# Main.net
KiCad netlist of a schematic drawn in Altium Designer
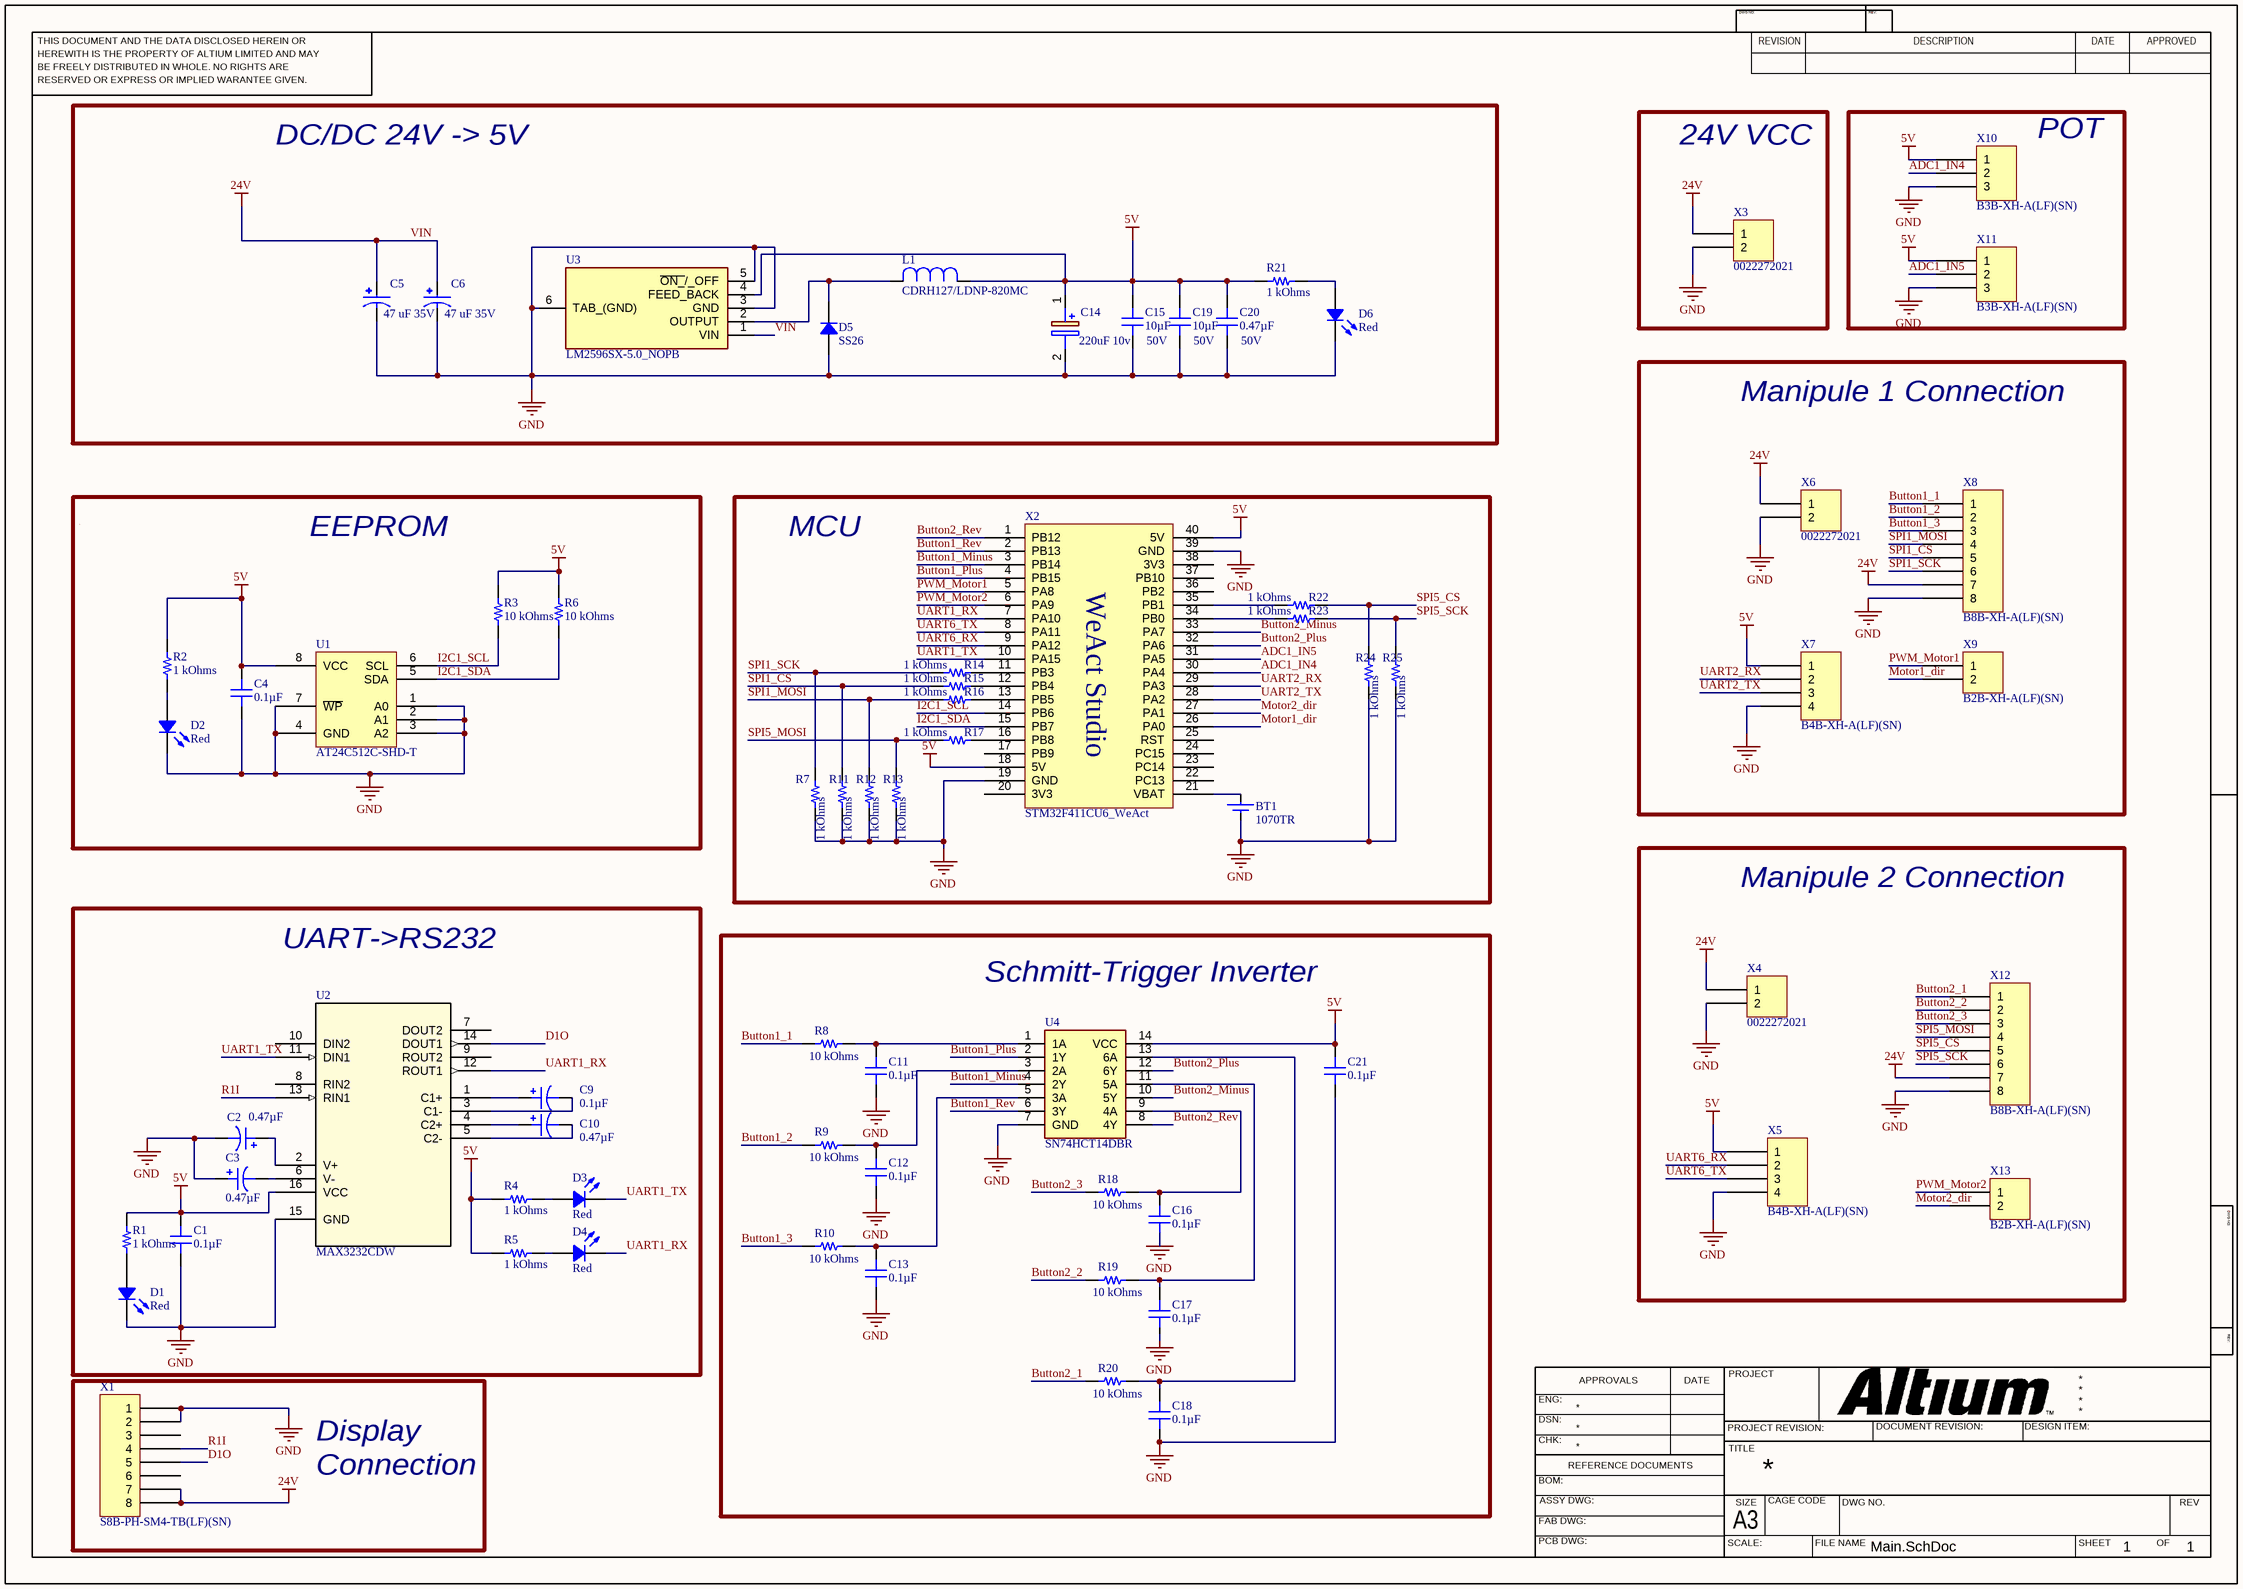
[diagram p0: Main.SchDoc]

(export (version "E")
  (design (tool "Eeschema 10.0.6"))
  (components
    (comp (ref "BT1")
      (value "1070TR")
      (footprint "SamacSys:1070TR")
      (description "Battery")
      (fields (field (name "MOUSER PART NUMBER") "534-1070TR"))
      (libsource (lib "SamacSys") (part "1070TR"))
    )
    (comp (ref "C1")
      (value "0.1µF")
      (footprint "CAP 0805_2012")
      (description "SMD AUTO X7R, CERAMIC, 0.1 UF, 1")
      (fields (field (name "PART NUMBER") "C0805C104K9RACAUTO") (field (name "MANUFACTURER") "KEMET"))
      (libsource (lib "Celestial Altium Library - altium_library") (part "Capacitor"))
    )
    (comp (ref "C2")
      (value "0.47µF")
      (footprint "CAP POL 1206_3216")
      (description "CAP TANT 0.47UF 10% 35V 1206")
      (fields (field (name "PART NUMBER") "293D474X9035A2TE3") (field (name "MANUFACTURER") "Vishay Sprague"))
      (libsource (lib "Celestial Altium Library - altium_library") (part "Polarised Capacitor"))
    )
    (comp (ref "C3")
      (value "0.47µF")
      (footprint "CAP POL 1206_3216")
      (description "CAP TANT 0.47UF 10% 35V 1206")
      (fields (field (name "PART NUMBER") "293D474X9035A2TE3") (field (name "MANUFACTURER") "Vishay Sprague"))
      (libsource (lib "Celestial Altium Library - altium_library") (part "Polarised Capacitor"))
    )
    (comp (ref "C4")
      (value "0.1µF")
      (footprint "CAP 0805_2012")
      (description "SMD AUTO X7R, CERAMIC, 0.1 UF, 1")
      (fields (field (name "PART NUMBER") "C0805C104K9RACAUTO") (field (name "MANUFACTURER") "KEMET"))
      (libsource (lib "Celestial Altium Library - altium_library") (part "Capacitor"))
    )
    (comp (ref "C5")
      (value "47 uF 35V")
      (footprint "CAP_EEHZA1V470P")
      (description "CAP ALUM POLY HYB 47UF 35V SMD")
      (fields
        (field (name "MF") "{'manufacturer': u'Panasonic Electronic'}")
        (field (name "MP") "EEHZA1V470P")
      )
      (libsource (lib "SnapEDA_Library") (part "EEHZA1V470P"))
    )
    (comp (ref "C6")
      (value "47 uF 35V")
      (footprint "CAP_EEHZA1V470P")
      (description "CAP ALUM POLY HYB 47UF 35V SMD")
      (fields
        (field (name "MF") "{'manufacturer': u'Panasonic Electronic'}")
        (field (name "MP") "EEHZA1V470P")
      )
      (libsource (lib "SnapEDA_Library") (part "EEHZA1V470P"))
    )
    (comp (ref "C9")
      (value "0.1µF")
      (footprint "CAP POL 1206_3216")
      (description "CAP TANT 0.1UF 20% 35V 1206")
      (fields (field (name "PART NUMBER") "293D104X0035A2TE3") (field (name "MANUFACTURER") "Vishay Sprague"))
      (libsource (lib "Celestial Altium Library - altium_library") (part "Polarised Capacitor"))
    )
    (comp (ref "C10")
      (value "0.47µF")
      (footprint "CAP POL 1206_3216")
      (description "CAP TANT 0.47UF 10% 35V 1206")
      (fields (field (name "PART NUMBER") "293D474X9035A2TE3") (field (name "MANUFACTURER") "Vishay Sprague"))
      (libsource (lib "Celestial Altium Library - altium_library") (part "Polarised Capacitor"))
    )
    (comp (ref "C11")
      (value "0.1µF")
      (footprint "CAP 0805_2012")
      (description "SMD AUTO X7R, CERAMIC, 0.1 UF, 1")
      (fields (field (name "PART NUMBER") "C0805C104K9RACAUTO") (field (name "MANUFACTURER") "KEMET"))
      (libsource (lib "Celestial Altium Library - altium_library") (part "Capacitor"))
    )
    (comp (ref "C12")
      (value "0.1µF")
      (footprint "CAP 0805_2012")
      (description "SMD AUTO X7R, CERAMIC, 0.1 UF, 1")
      (fields (field (name "PART NUMBER") "C0805C104K9RACAUTO") (field (name "MANUFACTURER") "KEMET"))
      (libsource (lib "Celestial Altium Library - altium_library") (part "Capacitor"))
    )
    (comp (ref "C13")
      (value "0.1µF")
      (footprint "CAP 0805_2012")
      (description "SMD AUTO X7R, CERAMIC, 0.1 UF, 1")
      (fields (field (name "PART NUMBER") "C0805C104K9RACAUTO") (field (name "MANUFACTURER") "KEMET"))
      (libsource (lib "Celestial Altium Library - altium_library") (part "Capacitor"))
    )
    (comp (ref "C14")
      (value "293D227X9010E2TE3")
      (footprint "SamacSys:CAPPM7343X430N")
      (description "Tantalum Capacitors - Solid SMD 220uF 10volts 10% E case Molded")
      (fields (field (name "MOUSER PART NUMBER") "220uF 10v"))
      (libsource (lib "*") (part "293D227X9010E2TE3"))
    )
    (comp (ref "C15")
      (value "10µF")
      (footprint "CAP 0805_2012")
      (description "0805 (2012MM) X5R (EIA) 50VDC 10")
      (fields
        (field (name "PART NUMBER") "GRM21BR61H106KE43L")
        (field (name "MANUFACTURER") "Murata Electronics")
        (field (name "VOLTAGE - RATED") "50V")
      )
      (libsource (lib "Celestial Altium Library - altium_library") (part "Capacitor"))
    )
    (comp (ref "C16")
      (value "0.1µF")
      (footprint "CAP 0805_2012")
      (description "SMD AUTO X7R, CERAMIC, 0.1 UF, 1")
      (fields (field (name "PART NUMBER") "C0805C104K9RACAUTO") (field (name "MANUFACTURER") "KEMET"))
      (libsource (lib "Celestial Altium Library - altium_library") (part "Capacitor"))
    )
    (comp (ref "C17")
      (value "0.1µF")
      (footprint "CAP 0805_2012")
      (description "SMD AUTO X7R, CERAMIC, 0.1 UF, 1")
      (fields (field (name "PART NUMBER") "C0805C104K9RACAUTO") (field (name "MANUFACTURER") "KEMET"))
      (libsource (lib "Celestial Altium Library - altium_library") (part "Capacitor"))
    )
    (comp (ref "C18")
      (value "0.1µF")
      (footprint "CAP 0805_2012")
      (description "SMD AUTO X7R, CERAMIC, 0.1 UF, 1")
      (fields (field (name "PART NUMBER") "C0805C104K9RACAUTO") (field (name "MANUFACTURER") "KEMET"))
      (libsource (lib "Celestial Altium Library - altium_library") (part "Capacitor"))
    )
    (comp (ref "C19")
      (value "10µF")
      (footprint "CAP 0805_2012")
      (description "0805 (2012MM) X5R (EIA) 50VDC 10")
      (fields
        (field (name "PART NUMBER") "GRM21BR61H106KE43L")
        (field (name "MANUFACTURER") "Murata Electronics")
        (field (name "VOLTAGE - RATED") "50V")
      )
      (libsource (lib "Celestial Altium Library - altium_library") (part "Capacitor"))
    )
    (comp (ref "C20")
      (value "0.47µF")
      (footprint "CAP 0805_2012")
      (description "CAP CER 0.47UF 50V X7R 0805")
      (fields
        (field (name "PART NUMBER") "GCM21BR71H474KA55L")
        (field (name "MANUFACTURER") "Murata Electronics")
        (field (name "VOLTAGE - RATED") "50V")
      )
      (libsource (lib "Celestial Altium Library - altium_library") (part "Capacitor"))
    )
    (comp (ref "C21")
      (value "0.1µF")
      (footprint "CAP 0805_2012")
      (description "SMD AUTO X7R, CERAMIC, 0.1 UF, 1")
      (fields (field (name "PART NUMBER") "C0805C104K9RACAUTO") (field (name "MANUFACTURER") "KEMET"))
      (libsource (lib "Celestial Altium Library - altium_library") (part "Capacitor"))
    )
    (comp (ref "D1")
      (value "Red")
      (footprint "LED 0603_1608 RED")
      (description "LED RED CLEAR 2SMD")
      (fields
        (field (name "PART NUMBER") "19-213USRC/S259/TR8")
        (field (name "MANUFACTURER") "Everlight Electronics Co Ltd")
      )
      (libsource (lib "Celestial Altium Library - altium_library") (part "LED"))
    )
    (comp (ref "D2")
      (value "Red")
      (footprint "LED 0603_1608 RED")
      (description "LED RED CLEAR 2SMD")
      (fields
        (field (name "PART NUMBER") "19-213USRC/S259/TR8")
        (field (name "MANUFACTURER") "Everlight Electronics Co Ltd")
      )
      (libsource (lib "Celestial Altium Library - altium_library") (part "LED"))
    )
    (comp (ref "D3")
      (value "Red")
      (footprint "LED 0603_1608 RED")
      (description "LED RED CLEAR 2SMD")
      (fields
        (field (name "PART NUMBER") "19-213USRC/S259/TR8")
        (field (name "MANUFACTURER") "Everlight Electronics Co Ltd")
      )
      (libsource (lib "Celestial Altium Library - altium_library") (part "LED"))
    )
    (comp (ref "D4")
      (value "Red")
      (footprint "LED 0603_1608 RED")
      (description "LED RED CLEAR 2SMD")
      (fields
        (field (name "PART NUMBER") "19-213USRC/S259/TR8")
        (field (name "MANUFACTURER") "Everlight Electronics Co Ltd")
      )
      (libsource (lib "Celestial Altium Library - altium_library") (part "LED"))
    )
    (comp (ref "D5")
      (value "SS26")
      (footprint "DO214AA SMB")
      (description "DIODE SCHOTTKY 60V 2A DO214AA")
      (fields (field (name "MANUFACTURER") "ON Semiconductor"))
      (libsource (lib "Celestial Altium Library - altium_library") (part "Diode"))
    )
    (comp (ref "D6")
      (value "Red")
      (footprint "LED 0603_1608 RED")
      (description "LED RED CLEAR 2SMD")
      (fields
        (field (name "PART NUMBER") "19-213USRC/S259/TR8")
        (field (name "MANUFACTURER") "Everlight Electronics Co Ltd")
      )
      (libsource (lib "Celestial Altium Library - altium_library") (part "LED"))
    )
    (comp (ref "L1")
      (value "CDRH127/LDNP-820MC")
      (footprint "IND_CDRH127/LDNP-470MC_SUM")
      (description "47 ÂµH Shielded - Inductor 3.25 A 78mOhm Max Nonstandard")
      (fields (field (name "MF") "Sumida America") (field (name "MP") "CDRH127/LDNP-470MC"))
      (libsource (lib "CDRH127_LDNP-470MC") (part "CDRH127/LDNP-470MC"))
    )
    (comp (ref "R1")
      (value "1 kOhms")
      (footprint "RES 0805_2012")
      (description "RES SMD 1K OHM 0.1% 1/8W 0805")
      (fields (field (name "PART NUMBER") "RT0805BRE071KL") (field (name "MANUFACTURER") "Yageo"))
      (libsource (lib "Celestial Altium Library - altium_library") (part "Resistor"))
    )
    (comp (ref "R2")
      (value "1 kOhms")
      (footprint "RES 0805_2012")
      (description "RES SMD 1K OHM 0.1% 1/8W 0805")
      (fields (field (name "PART NUMBER") "RT0805BRE071KL") (field (name "MANUFACTURER") "Yageo"))
      (libsource (lib "Celestial Altium Library - altium_library") (part "Resistor"))
    )
    (comp (ref "R3")
      (value "10 kOhms")
      (footprint "RES 0805_2012")
      (description "RES SMD 10K OHM 0.5% 1/8W 0805")
      (fields (field (name "PART NUMBER") "RT0805DRD0710KL") (field (name "MANUFACTURER") "Yageo"))
      (libsource (lib "Celestial Altium Library - altium_library") (part "Resistor"))
    )
    (comp (ref "R4")
      (value "1 kOhms")
      (footprint "RES 0805_2012")
      (description "RES SMD 1K OHM 0.1% 1/8W 0805")
      (fields (field (name "PART NUMBER") "RT0805BRE071KL") (field (name "MANUFACTURER") "Yageo"))
      (libsource (lib "Celestial Altium Library - altium_library") (part "Resistor"))
    )
    (comp (ref "R5")
      (value "1 kOhms")
      (footprint "RES 0805_2012")
      (description "RES SMD 1K OHM 0.1% 1/8W 0805")
      (fields (field (name "PART NUMBER") "RT0805BRE071KL") (field (name "MANUFACTURER") "Yageo"))
      (libsource (lib "Celestial Altium Library - altium_library") (part "Resistor"))
    )
    (comp (ref "R6")
      (value "10 kOhms")
      (footprint "RES 0805_2012")
      (description "RES SMD 10K OHM 0.5% 1/8W 0805")
      (fields (field (name "PART NUMBER") "RT0805DRD0710KL") (field (name "MANUFACTURER") "Yageo"))
      (libsource (lib "Celestial Altium Library - altium_library") (part "Resistor"))
    )
    (comp (ref "R7")
      (value "1 kOhms")
      (footprint "RES 0805_2012")
      (description "RES SMD 1K OHM 0.1% 1/8W 0805")
      (fields (field (name "PART NUMBER") "RT0805BRE071KL") (field (name "MANUFACTURER") "Yageo"))
      (libsource (lib "Celestial Altium Library - altium_library") (part "Resistor"))
    )
    (comp (ref "R8")
      (value "10 kOhms")
      (footprint "RES 0805_2012")
      (description "RES SMD 10K OHM 0.5% 1/8W 0805")
      (fields (field (name "PART NUMBER") "RT0805DRD0710KL") (field (name "MANUFACTURER") "Yageo"))
      (libsource (lib "Celestial Altium Library - altium_library") (part "Resistor"))
    )
    (comp (ref "R9")
      (value "10 kOhms")
      (footprint "RES 0805_2012")
      (description "RES SMD 10K OHM 0.5% 1/8W 0805")
      (fields (field (name "PART NUMBER") "RT0805DRD0710KL") (field (name "MANUFACTURER") "Yageo"))
      (libsource (lib "Celestial Altium Library - altium_library") (part "Resistor"))
    )
    (comp (ref "R10")
      (value "10 kOhms")
      (footprint "RES 0805_2012")
      (description "RES SMD 10K OHM 0.5% 1/8W 0805")
      (fields (field (name "PART NUMBER") "RT0805DRD0710KL") (field (name "MANUFACTURER") "Yageo"))
      (libsource (lib "Celestial Altium Library - altium_library") (part "Resistor"))
    )
    (comp (ref "R11")
      (value "1 kOhms")
      (footprint "RES 0805_2012")
      (description "RES SMD 1K OHM 0.1% 1/8W 0805")
      (fields (field (name "PART NUMBER") "RT0805BRE071KL") (field (name "MANUFACTURER") "Yageo"))
      (libsource (lib "Celestial Altium Library - altium_library") (part "Resistor"))
    )
    (comp (ref "R12")
      (value "1 kOhms")
      (footprint "RES 0805_2012")
      (description "RES SMD 1K OHM 0.1% 1/8W 0805")
      (fields (field (name "PART NUMBER") "RT0805BRE071KL") (field (name "MANUFACTURER") "Yageo"))
      (libsource (lib "Celestial Altium Library - altium_library") (part "Resistor"))
    )
    (comp (ref "R13")
      (value "1 kOhms")
      (footprint "RES 0805_2012")
      (description "RES SMD 1K OHM 0.1% 1/8W 0805")
      (fields (field (name "PART NUMBER") "RT0805BRE071KL") (field (name "MANUFACTURER") "Yageo"))
      (libsource (lib "Celestial Altium Library - altium_library") (part "Resistor"))
    )
    (comp (ref "R14")
      (value "1 kOhms")
      (footprint "RES 0805_2012")
      (description "RES SMD 1K OHM 0.1% 1/8W 0805")
      (fields (field (name "PART NUMBER") "RT0805BRE071KL") (field (name "MANUFACTURER") "Yageo"))
      (libsource (lib "Celestial Altium Library - altium_library") (part "Resistor"))
    )
    (comp (ref "R15")
      (value "1 kOhms")
      (footprint "RES 0805_2012")
      (description "RES SMD 1K OHM 0.1% 1/8W 0805")
      (fields (field (name "PART NUMBER") "RT0805BRE071KL") (field (name "MANUFACTURER") "Yageo"))
      (libsource (lib "Celestial Altium Library - altium_library") (part "Resistor"))
    )
    (comp (ref "R16")
      (value "1 kOhms")
      (footprint "RES 0805_2012")
      (description "RES SMD 1K OHM 0.1% 1/8W 0805")
      (fields (field (name "PART NUMBER") "RT0805BRE071KL") (field (name "MANUFACTURER") "Yageo"))
      (libsource (lib "Celestial Altium Library - altium_library") (part "Resistor"))
    )
    (comp (ref "R17")
      (value "1 kOhms")
      (footprint "RES 0805_2012")
      (description "RES SMD 1K OHM 0.1% 1/8W 0805")
      (fields (field (name "PART NUMBER") "RT0805BRE071KL") (field (name "MANUFACTURER") "Yageo"))
      (libsource (lib "Celestial Altium Library - altium_library") (part "Resistor"))
    )
    (comp (ref "R18")
      (value "10 kOhms")
      (footprint "RES 0805_2012")
      (description "RES SMD 10K OHM 0.5% 1/8W 0805")
      (fields (field (name "PART NUMBER") "RT0805DRD0710KL") (field (name "MANUFACTURER") "Yageo"))
      (libsource (lib "Celestial Altium Library - altium_library") (part "Resistor"))
    )
    (comp (ref "R19")
      (value "10 kOhms")
      (footprint "RES 0805_2012")
      (description "RES SMD 10K OHM 0.5% 1/8W 0805")
      (fields (field (name "PART NUMBER") "RT0805DRD0710KL") (field (name "MANUFACTURER") "Yageo"))
      (libsource (lib "Celestial Altium Library - altium_library") (part "Resistor"))
    )
    (comp (ref "R20")
      (value "10 kOhms")
      (footprint "RES 0805_2012")
      (description "RES SMD 10K OHM 0.5% 1/8W 0805")
      (fields (field (name "PART NUMBER") "RT0805DRD0710KL") (field (name "MANUFACTURER") "Yageo"))
      (libsource (lib "Celestial Altium Library - altium_library") (part "Resistor"))
    )
    (comp (ref "R21")
      (value "1 kOhms")
      (footprint "RES 0805_2012")
      (description "RES SMD 1K OHM 0.1% 1/8W 0805")
      (fields (field (name "PART NUMBER") "RT0805BRE071KL") (field (name "MANUFACTURER") "Yageo"))
      (libsource (lib "Celestial Altium Library - altium_library") (part "Resistor"))
    )
    (comp (ref "R22")
      (value "1 kOhms")
      (footprint "RES 0805_2012")
      (description "RES SMD 1K OHM 0.1% 1/8W 0805")
      (fields (field (name "PART NUMBER") "RT0805BRE071KL") (field (name "MANUFACTURER") "Yageo"))
      (libsource (lib "Celestial Altium Library - altium_library") (part "Resistor"))
    )
    (comp (ref "R23")
      (value "1 kOhms")
      (footprint "RES 0805_2012")
      (description "RES SMD 1K OHM 0.1% 1/8W 0805")
      (fields (field (name "PART NUMBER") "RT0805BRE071KL") (field (name "MANUFACTURER") "Yageo"))
      (libsource (lib "Celestial Altium Library - altium_library") (part "Resistor"))
    )
    (comp (ref "R24")
      (value "1 kOhms")
      (footprint "RES 0805_2012")
      (description "RES SMD 1K OHM 0.1% 1/8W 0805")
      (fields (field (name "PART NUMBER") "RT0805BRE071KL") (field (name "MANUFACTURER") "Yageo"))
      (libsource (lib "Celestial Altium Library - altium_library") (part "Resistor"))
    )
    (comp (ref "R25")
      (value "1 kOhms")
      (footprint "RES 0805_2012")
      (description "RES SMD 1K OHM 0.1% 1/8W 0805")
      (fields (field (name "PART NUMBER") "RT0805BRE071KL") (field (name "MANUFACTURER") "Yageo"))
      (libsource (lib "Celestial Altium Library - altium_library") (part "Resistor"))
    )
    (comp (ref "U1")
      (value "AT24C512C-SHD-T")
      (footprint "MICROCHIP SOIC-8 208MIL WIDE")
      (description "IC EEPROM 512K I2C 1MHZ 8SOIC")
      (fields (field (name "MANUFACTURER") "Microchip Technology"))
      (libsource (lib "Celestial Altium Library - altium_library") (part "MICROCHIP EEPROM I2C 8PIN"))
    )
    (comp (ref "U2")
      (value "MAX3232CDW")
      (footprint "DW16")
      (description "No Description Available")
      (fields (field (name "COPYRIGHT") "Copyright (C) 2022 Ultra Librarian. All rights reserved."))
      (libsource (lib "MAX3232CDW") (part "MAX3232CDW"))
    )
    (comp (ref "U3")
      (value "LM2596SX-5.0_NOPB")
      (footprint "SamacSys:KTT0005B")
      (description "Integrated Circuit")
      (fields
        (field (name "MANUFACTURER_PART_NUMBER") "LM2596SX-5.0/NOPB")
        (field (name "MOUSER PART NUMBER") "926-LM2596SX-5.0NOPB")
      )
      (libsource (lib "*") (part "LM2596SX-5.0_NOPB"))
    )
    (comp (ref "U4")
      (value "SN74HCT14DBR")
      (footprint "SamacSys:SOP65P780X200-14N")
      (description "Integrated Circuit")
      (fields (field (name "MOUSER PART NUMBER") "595-SN74HCT14DBR"))
      (libsource (lib "*") (part "SN74HCT14DBR"))
    )
    (comp (ref "X1")
      (value "S8B-PH-SM4-TB(LF)(SN)")
      (footprint "JST S8B-PH-SM4-TB")
      (description "CONN HEADER SMD R/A 8POS 2MM")
      (fields (field (name "MANUFACTURER") "JST Sales America Inc."))
      (libsource (lib "") (part "8 Pin_1"))
    )
    (comp (ref "X2")
      (value "STM32F411CU6_WeAct")
      (footprint "STM32F4x1CxU6 WeActStudio")
      (libsource (lib "Lib_Massage") (part "STM32F411CU6_WeAct"))
    )
    (comp (ref "X3")
      (value "0022272021")
      (footprint "MOLEX KK 0022272021")
      (description "CONN HEADER VERT 2POS 2.54MM")
      (fields (field (name "MANUFACTURER") "Molex"))
      (libsource (lib "Celestial Altium Library - altium_library") (part "2 Pin"))
    )
    (comp (ref "X4")
      (value "0022272021")
      (footprint "MOLEX KK 0022272021")
      (description "CONN HEADER VERT 2POS 2.54MM")
      (fields (field (name "MANUFACTURER") "Molex"))
      (libsource (lib "Celestial Altium Library - altium_library") (part "2 Pin"))
    )
    (comp (ref "X5")
      (value "B4B-XH-A(LF)(SN)")
      (footprint "JST XH B4B-XH-A")
      (description "CONN HEADER VERT 4POS 2.5MM")
      (fields (field (name "MANUFACTURER") "JST Sales America Inc."))
      (libsource (lib "Celestial Altium Library - altium_library") (part "4 Pin"))
    )
    (comp (ref "X6")
      (value "0022272021")
      (footprint "MOLEX KK 0022272021")
      (description "CONN HEADER VERT 2POS 2.54MM")
      (fields (field (name "MANUFACTURER") "Molex"))
      (libsource (lib "Celestial Altium Library - altium_library") (part "2 Pin"))
    )
    (comp (ref "X7")
      (value "B4B-XH-A(LF)(SN)")
      (footprint "JST XH B4B-XH-A")
      (description "CONN HEADER VERT 4POS 2.5MM")
      (fields (field (name "MANUFACTURER") "JST Sales America Inc."))
      (libsource (lib "Celestial Altium Library - altium_library") (part "4 Pin"))
    )
    (comp (ref "X8")
      (value "B8B-XH-A(LF)(SN)")
      (footprint "JST XH B8B-XH-A")
      (description "CONN HEADER VERT 8POS 2.5MM")
      (fields (field (name "MANUFACTURER") "JST Sales America Inc."))
      (libsource (lib "Celestial Altium Library - altium_library") (part "8 Pin"))
    )
    (comp (ref "X9")
      (value "B2B-XH-A(LF)(SN)")
      (footprint "JST XH B2B-XH-A")
      (description "CONN HEADER VERT 2POS 2.5MM")
      (fields (field (name "MANUFACTURER") "JST Sales America Inc."))
      (libsource (lib "Celestial Altium Library - altium_library") (part "2 Pin"))
    )
    (comp (ref "X10")
      (value "B3B-XH-A(LF)(SN)")
      (footprint "JST XH B3B-XH-A")
      (description "CONN HEADER VERT 3POS 2.5MM")
      (fields (field (name "MANUFACTURER") "JST Sales America Inc."))
      (libsource (lib "Celestial Altium Library - altium_library") (part "3 Pin"))
    )
    (comp (ref "X11")
      (value "B3B-XH-A(LF)(SN)")
      (footprint "JST XH B3B-XH-A")
      (description "CONN HEADER VERT 3POS 2.5MM")
      (fields (field (name "MANUFACTURER") "JST Sales America Inc."))
      (libsource (lib "Celestial Altium Library - altium_library") (part "3 Pin"))
    )
    (comp (ref "X12")
      (value "B8B-XH-A(LF)(SN)")
      (footprint "JST XH B8B-XH-A")
      (description "CONN HEADER VERT 8POS 2.5MM")
      (fields (field (name "MANUFACTURER") "JST Sales America Inc."))
      (libsource (lib "Celestial Altium Library - altium_library") (part "8 Pin"))
    )
    (comp (ref "X13")
      (value "B2B-XH-A(LF)(SN)")
      (footprint "JST XH B2B-XH-A")
      (description "CONN HEADER VERT 2POS 2.5MM")
      (fields (field (name "MANUFACTURER") "JST Sales America Inc."))
      (libsource (lib "Celestial Altium Library - altium_library") (part "2 Pin"))
    )
  )
  (nets
    (net (code "1") (name "/ADC1_IN4") (class "Default")
      (node (ref "X10") (pin "2") (pinfunction "2_2") (pintype "passive"))
      (node (ref "X2") (pin "30") (pinfunction "PA4_30") (pintype "passive"))
    )
    (net (code "2") (name "/ADC1_IN5") (class "Default")
      (node (ref "X11") (pin "2") (pinfunction "2_2") (pintype "passive"))
      (node (ref "X2") (pin "31") (pinfunction "PA5_31") (pintype "passive"))
    )
    (net (code "3") (name "/Button1_1") (class "Default")
      (node (ref "R8") (pin "2") (pinfunction "2_2") (pintype "passive"))
      (node (ref "X8") (pin "1") (pinfunction "1_1") (pintype "passive"))
    )
    (net (code "4") (name "/Button1_2") (class "Default")
      (node (ref "R9") (pin "2") (pinfunction "2_2") (pintype "passive"))
      (node (ref "X8") (pin "2") (pinfunction "2_2") (pintype "passive"))
    )
    (net (code "5") (name "/Button1_3") (class "Default")
      (node (ref "R10") (pin "2") (pinfunction "2_2") (pintype "passive"))
      (node (ref "X8") (pin "3") (pinfunction "3_3") (pintype "passive"))
    )
    (net (code "6") (name "/Button1_Minus") (class "Default")
      (node (ref "U4") (pin "4") (pinfunction "2Y_4") (pintype "passive"))
      (node (ref "X2") (pin "3") (pinfunction "PB14_3") (pintype "passive"))
    )
    (net (code "7") (name "/Button1_Plus") (class "Default")
      (node (ref "U4") (pin "2") (pinfunction "1Y_2") (pintype "passive"))
      (node (ref "X2") (pin "4") (pinfunction "PB15_4") (pintype "passive"))
    )
    (net (code "8") (name "/Button1_Rev") (class "Default")
      (node (ref "U4") (pin "6") (pinfunction "3Y_6") (pintype "passive"))
      (node (ref "X2") (pin "2") (pinfunction "PB13_2") (pintype "passive"))
    )
    (net (code "9") (name "/Button2_1") (class "Default")
      (node (ref "R20") (pin "2") (pinfunction "2_2") (pintype "passive"))
      (node (ref "X12") (pin "1") (pinfunction "1_1") (pintype "passive"))
    )
    (net (code "10") (name "/Button2_2") (class "Default")
      (node (ref "R19") (pin "2") (pinfunction "2_2") (pintype "passive"))
      (node (ref "X12") (pin "2") (pinfunction "2_2") (pintype "passive"))
    )
    (net (code "11") (name "/Button2_3") (class "Default")
      (node (ref "R18") (pin "2") (pinfunction "2_2") (pintype "passive"))
      (node (ref "X12") (pin "3") (pinfunction "3_3") (pintype "passive"))
    )
    (net (code "12") (name "/Button2_Minus") (class "Default")
      (node (ref "U4") (pin "10") (pinfunction "5Y_10") (pintype "passive"))
      (node (ref "X2") (pin "33") (pinfunction "PA7_33") (pintype "passive"))
    )
    (net (code "13") (name "/Button2_Plus") (class "Default")
      (node (ref "U4") (pin "12") (pinfunction "6Y_12") (pintype "passive"))
      (node (ref "X2") (pin "32") (pinfunction "PA6_32") (pintype "passive"))
    )
    (net (code "14") (name "/Button2_Rev") (class "Default")
      (node (ref "U4") (pin "8") (pinfunction "4Y_8") (pintype "passive"))
      (node (ref "X2") (pin "1") (pinfunction "PB12_1") (pintype "passive"))
    )
    (net (code "15") (name "/D1O") (class "Default")
      (node (ref "U2") (pin "14") (pinfunction "DOUT1_14") (pintype "output"))
      (node (ref "X1") (pin "5") (pinfunction "5_5") (pintype "passive"))
    )
    (net (code "16") (name "/I2C1_SCL") (class "Default")
      (node (ref "R3") (pin "1") (pinfunction "1_1") (pintype "passive"))
      (node (ref "U1") (pin "6") (pinfunction "SCL_6") (pintype "passive"))
      (node (ref "X2") (pin "14") (pinfunction "PB6_14") (pintype "passive"))
    )
    (net (code "17") (name "/I2C1_SDA") (class "Default")
      (node (ref "R6") (pin "1") (pinfunction "1_1") (pintype "passive"))
      (node (ref "U1") (pin "5") (pinfunction "SDA_5") (pintype "passive"))
      (node (ref "X2") (pin "15") (pinfunction "PB7_15") (pintype "passive"))
    )
    (net (code "18") (name "/Motor1_dir") (class "Default")
      (node (ref "X2") (pin "26") (pinfunction "PA0_26") (pintype "passive"))
      (node (ref "X9") (pin "2") (pinfunction "2_2") (pintype "passive"))
    )
    (net (code "19") (name "/Motor2_dir") (class "Default")
      (node (ref "X13") (pin "2") (pinfunction "2_2") (pintype "passive"))
      (node (ref "X2") (pin "27") (pinfunction "PA1_27") (pintype "passive"))
    )
    (net (code "20") (name "/PWM_Motor1") (class "Default")
      (node (ref "X2") (pin "5") (pinfunction "PA8_5") (pintype "passive"))
      (node (ref "X9") (pin "1") (pinfunction "1_1") (pintype "passive"))
    )
    (net (code "21") (name "/PWM_Motor2") (class "Default")
      (node (ref "X13") (pin "1") (pinfunction "1_1") (pintype "passive"))
      (node (ref "X2") (pin "6") (pinfunction "PA9_6") (pintype "passive"))
    )
    (net (code "22") (name "/R1I") (class "Default")
      (node (ref "U2") (pin "13") (pinfunction "RIN1_13") (pintype "input"))
      (node (ref "X1") (pin "4") (pinfunction "4_4") (pintype "passive"))
    )
    (net (code "23") (name "/SPI1_CS") (class "Default")
      (node (ref "R11") (pin "1") (pinfunction "1_1") (pintype "passive"))
      (node (ref "R15") (pin "2") (pinfunction "2_2") (pintype "passive"))
      (node (ref "X8") (pin "5") (pinfunction "5_5") (pintype "passive"))
    )
    (net (code "24") (name "/SPI1_MOSI") (class "Default")
      (node (ref "R12") (pin "1") (pinfunction "1_1") (pintype "passive"))
      (node (ref "R16") (pin "2") (pinfunction "2_2") (pintype "passive"))
      (node (ref "X8") (pin "4") (pinfunction "4_4") (pintype "passive"))
    )
    (net (code "25") (name "/SPI1_SCK") (class "Default")
      (node (ref "R14") (pin "2") (pinfunction "2_2") (pintype "passive"))
      (node (ref "R7") (pin "1") (pinfunction "1_1") (pintype "passive"))
      (node (ref "X8") (pin "6") (pinfunction "6_6") (pintype "passive"))
    )
    (net (code "26") (name "/SPI5_CS") (class "Default")
      (node (ref "R22") (pin "1") (pinfunction "1_1") (pintype "passive"))
      (node (ref "R24") (pin "1") (pinfunction "1_1") (pintype "passive"))
      (node (ref "X12") (pin "5") (pinfunction "5_5") (pintype "passive"))
    )
    (net (code "27") (name "/SPI5_MOSI") (class "Default")
      (node (ref "R13") (pin "1") (pinfunction "1_1") (pintype "passive"))
      (node (ref "R17") (pin "2") (pinfunction "2_2") (pintype "passive"))
      (node (ref "X12") (pin "4") (pinfunction "4_4") (pintype "passive"))
    )
    (net (code "28") (name "/SPI5_SCK") (class "Default")
      (node (ref "R23") (pin "1") (pinfunction "1_1") (pintype "passive"))
      (node (ref "R25") (pin "1") (pinfunction "1_1") (pintype "passive"))
      (node (ref "X12") (pin "6") (pinfunction "6_6") (pintype "passive"))
    )
    (net (code "29") (name "/UART1_RX") (class "Default")
      (node (ref "D4") (pin "2") (pinfunction "2_2") (pintype "passive"))
      (node (ref "U2") (pin "12") (pinfunction "ROUT1_12") (pintype "output"))
      (node (ref "X2") (pin "7") (pinfunction "PA10_7") (pintype "passive"))
    )
    (net (code "30") (name "/UART1_TX") (class "Default")
      (node (ref "D3") (pin "2") (pinfunction "2_2") (pintype "passive"))
      (node (ref "U2") (pin "11") (pinfunction "DIN1_11") (pintype "input"))
      (node (ref "X2") (pin "10") (pinfunction "PA15_10") (pintype "passive"))
    )
    (net (code "31") (name "/UART2_RX") (class "Default")
      (node (ref "X2") (pin "29") (pinfunction "PA3_29") (pintype "passive"))
      (node (ref "X7") (pin "2") (pinfunction "2_2") (pintype "passive"))
    )
    (net (code "32") (name "/UART2_TX") (class "Default")
      (node (ref "X2") (pin "28") (pinfunction "PA2_28") (pintype "passive"))
      (node (ref "X7") (pin "3") (pinfunction "3_3") (pintype "passive"))
    )
    (net (code "33") (name "/UART6_RX") (class "Default")
      (node (ref "X2") (pin "9") (pinfunction "PA12_9") (pintype "passive"))
      (node (ref "X5") (pin "2") (pinfunction "2_2") (pintype "passive"))
    )
    (net (code "34") (name "/UART6_TX") (class "Default")
      (node (ref "X2") (pin "8") (pinfunction "PA11_8") (pintype "passive"))
      (node (ref "X5") (pin "3") (pinfunction "3_3") (pintype "passive"))
    )
    (net (code "35") (name "5V") (class "Default")
      (node (ref "C1") (pin "2") (pinfunction "2_2") (pintype "passive"))
      (node (ref "C14") (pin "1") (pinfunction "+_1") (pintype "passive"))
      (node (ref "C15") (pin "1") (pinfunction "1_1") (pintype "passive"))
      (node (ref "C19") (pin "1") (pinfunction "1_1") (pintype "passive"))
      (node (ref "C20") (pin "2") (pinfunction "2_2") (pintype "passive"))
      (node (ref "C21") (pin "2") (pinfunction "2_2") (pintype "passive"))
      (node (ref "C4") (pin "2") (pinfunction "2_2") (pintype "passive"))
      (node (ref "L1") (pin "1") (pinfunction "1_1") (pintype "passive"))
      (node (ref "R1") (pin "2") (pinfunction "2_2") (pintype "passive"))
      (node (ref "R2") (pin "2") (pinfunction "2_2") (pintype "passive"))
      (node (ref "R21") (pin "2") (pinfunction "2_2") (pintype "passive"))
      (node (ref "R3") (pin "2") (pinfunction "2_2") (pintype "passive"))
      (node (ref "R4") (pin "2") (pinfunction "2_2") (pintype "passive"))
      (node (ref "R5") (pin "2") (pinfunction "2_2") (pintype "passive"))
      (node (ref "R6") (pin "2") (pinfunction "2_2") (pintype "passive"))
      (node (ref "U1") (pin "8") (pinfunction "VCC_8") (pintype "passive"))
      (node (ref "U2") (pin "16") (pinfunction "VCC_16") (pintype "power_in"))
      (node (ref "U3") (pin "4") (pinfunction "FEED_BACK_4") (pintype "passive"))
      (node (ref "U4") (pin "14") (pinfunction "VCC_14") (pintype "passive"))
      (node (ref "X10") (pin "1") (pinfunction "1_1") (pintype "passive"))
      (node (ref "X11") (pin "1") (pinfunction "1_1") (pintype "passive"))
      (node (ref "X2") (pin "18") (pinfunction "5V_18") (pintype "passive"))
      (node (ref "X2") (pin "40") (pinfunction "5V_40") (pintype "passive"))
      (node (ref "X5") (pin "1") (pinfunction "1_1") (pintype "passive"))
      (node (ref "X7") (pin "1") (pinfunction "1_1") (pintype "passive"))
    )
    (net (code "36") (name "24V") (class "Default")
      (node (ref "C5") (pin "1") (pinfunction "1_1") (pintype "passive"))
      (node (ref "C6") (pin "1") (pinfunction "1_1") (pintype "passive"))
      (node (ref "U3") (pin "1") (pinfunction "VIN_1") (pintype "passive"))
      (node (ref "X1") (pin "7") (pinfunction "7_7") (pintype "passive"))
      (node (ref "X1") (pin "8") (pinfunction "8_8") (pintype "passive"))
      (node (ref "X12") (pin "7") (pinfunction "7_7") (pintype "passive"))
      (node (ref "X3") (pin "1") (pinfunction "1_1") (pintype "passive"))
      (node (ref "X4") (pin "1") (pinfunction "1_1") (pintype "passive"))
      (node (ref "X6") (pin "1") (pinfunction "1_1") (pintype "passive"))
      (node (ref "X8") (pin "7") (pinfunction "7_7") (pintype "passive"))
    )
    (net (code "37") (name "GND") (class "Default")
      (node (ref "BT1") (pin "2") (pinfunction "-_2") (pintype "power_in"))
      (node (ref "C1") (pin "1") (pinfunction "1_1") (pintype "passive"))
      (node (ref "C11") (pin "1") (pinfunction "1_1") (pintype "passive"))
      (node (ref "C12") (pin "1") (pinfunction "1_1") (pintype "passive"))
      (node (ref "C13") (pin "1") (pinfunction "1_1") (pintype "passive"))
      (node (ref "C14") (pin "2") (pinfunction "-_2") (pintype "passive"))
      (node (ref "C15") (pin "2") (pinfunction "2_2") (pintype "passive"))
      (node (ref "C16") (pin "1") (pinfunction "1_1") (pintype "passive"))
      (node (ref "C17") (pin "1") (pinfunction "1_1") (pintype "passive"))
      (node (ref "C18") (pin "1") (pinfunction "1_1") (pintype "passive"))
      (node (ref "C19") (pin "2") (pinfunction "2_2") (pintype "passive"))
      (node (ref "C2") (pin "2") (pinfunction "2_2") (pintype "passive"))
      (node (ref "C20") (pin "1") (pinfunction "1_1") (pintype "passive"))
      (node (ref "C21") (pin "1") (pinfunction "1_1") (pintype "passive"))
      (node (ref "C3") (pin "1") (pinfunction "1_1") (pintype "passive"))
      (node (ref "C4") (pin "1") (pinfunction "1_1") (pintype "passive"))
      (node (ref "C5") (pin "2") (pinfunction "2_2") (pintype "passive"))
      (node (ref "C6") (pin "2") (pinfunction "2_2") (pintype "passive"))
      (node (ref "D1") (pin "2") (pinfunction "2_2") (pintype "passive"))
      (node (ref "D2") (pin "2") (pinfunction "2_2") (pintype "passive"))
      (node (ref "D5") (pin "1") (pinfunction "1_1") (pintype "passive"))
      (node (ref "D6") (pin "2") (pinfunction "2_2") (pintype "passive"))
      (node (ref "R11") (pin "2") (pinfunction "2_2") (pintype "passive"))
      (node (ref "R12") (pin "2") (pinfunction "2_2") (pintype "passive"))
      (node (ref "R13") (pin "2") (pinfunction "2_2") (pintype "passive"))
      (node (ref "R24") (pin "2") (pinfunction "2_2") (pintype "passive"))
      (node (ref "R25") (pin "2") (pinfunction "2_2") (pintype "passive"))
      (node (ref "R7") (pin "2") (pinfunction "2_2") (pintype "passive"))
      (node (ref "U1") (pin "1") (pinfunction "A0_1") (pintype "passive"))
      (node (ref "U1") (pin "2") (pinfunction "A1_2") (pintype "passive"))
      (node (ref "U1") (pin "3") (pinfunction "A2_3") (pintype "passive"))
      (node (ref "U1") (pin "4") (pinfunction "GND_4") (pintype "passive"))
      (node (ref "U1") (pin "7") (pinfunction "~{WP}_7") (pintype "passive"))
      (node (ref "U2") (pin "15") (pinfunction "GND_15") (pintype "power_in"))
      (node (ref "U3") (pin "3") (pinfunction "GND_3") (pintype "passive"))
      (node (ref "U3") (pin "5") (pinfunction "~{ON_}/_OFF_5") (pintype "passive"))
      (node (ref "U3") (pin "6") (pinfunction "TAB_(GND)_6") (pintype "passive"))
      (node (ref "U4") (pin "7") (pinfunction "GND_7") (pintype "passive"))
      (node (ref "X1") (pin "1") (pinfunction "1_1") (pintype "passive"))
      (node (ref "X1") (pin "2") (pinfunction "2_2") (pintype "passive"))
      (node (ref "X10") (pin "3") (pinfunction "3_3") (pintype "passive"))
      (node (ref "X11") (pin "3") (pinfunction "3_3") (pintype "passive"))
      (node (ref "X12") (pin "8") (pinfunction "8_8") (pintype "passive"))
      (node (ref "X2") (pin "19") (pinfunction "GND_19") (pintype "passive"))
      (node (ref "X2") (pin "39") (pinfunction "GND_39") (pintype "passive"))
      (node (ref "X3") (pin "2") (pinfunction "2_2") (pintype "passive"))
      (node (ref "X4") (pin "2") (pinfunction "2_2") (pintype "passive"))
      (node (ref "X5") (pin "4") (pinfunction "4_4") (pintype "passive"))
      (node (ref "X6") (pin "2") (pinfunction "2_2") (pintype "passive"))
      (node (ref "X7") (pin "4") (pinfunction "4_4") (pintype "passive"))
      (node (ref "X8") (pin "8") (pinfunction "8_8") (pintype "passive"))
    )
    (net (code "38") (name "Net-(BT1-+)") (class "Default")
      (node (ref "BT1") (pin "1") (pinfunction "+_1") (pintype "power_in"))
      (node (ref "X2") (pin "21") (pinfunction "VBAT_21") (pintype "passive"))
    )
    (net (code "39") (name "Net-(D1-Pad1)") (class "Default")
      (node (ref "D1") (pin "1") (pinfunction "1_1") (pintype "passive"))
      (node (ref "R1") (pin "1") (pinfunction "1_1") (pintype "passive"))
    )
    (net (code "40") (name "Net-(D2-Pad1)") (class "Default")
      (node (ref "D2") (pin "1") (pinfunction "1_1") (pintype "passive"))
      (node (ref "R2") (pin "1") (pinfunction "1_1") (pintype "passive"))
    )
    (net (code "41") (name "Net-(D3-Pad1)") (class "Default")
      (node (ref "D3") (pin "1") (pinfunction "1_1") (pintype "passive"))
      (node (ref "R4") (pin "1") (pinfunction "1_1") (pintype "passive"))
    )
    (net (code "42") (name "Net-(D4-Pad1)") (class "Default")
      (node (ref "D4") (pin "1") (pinfunction "1_1") (pintype "passive"))
      (node (ref "R5") (pin "1") (pinfunction "1_1") (pintype "passive"))
    )
    (net (code "43") (name "Net-(D6-Pad1)") (class "Default")
      (node (ref "D6") (pin "1") (pinfunction "1_1") (pintype "passive"))
      (node (ref "R21") (pin "1") (pinfunction "1_1") (pintype "passive"))
    )
    (net (code "44") (name "Net-(U2-C1+)") (class "Default")
      (node (ref "C9") (pin "1") (pinfunction "1_1") (pintype "passive"))
      (node (ref "U2") (pin "1") (pinfunction "C1+_1") (pintype "passive"))
    )
    (net (code "45") (name "Net-(U2-C1-)") (class "Default")
      (node (ref "C9") (pin "2") (pinfunction "2_2") (pintype "passive"))
      (node (ref "U2") (pin "3") (pinfunction "C1-_3") (pintype "passive"))
    )
    (net (code "46") (name "Net-(U2-C2+)") (class "Default")
      (node (ref "C10") (pin "1") (pinfunction "1_1") (pintype "passive"))
      (node (ref "U2") (pin "4") (pinfunction "C2+_4") (pintype "passive"))
    )
    (net (code "47") (name "Net-(U2-C2-)") (class "Default")
      (node (ref "C10") (pin "2") (pinfunction "2_2") (pintype "passive"))
      (node (ref "U2") (pin "5") (pinfunction "C2-_5") (pintype "passive"))
    )
    (net (code "48") (name "Net-(U2-V+)") (class "Default")
      (node (ref "C2") (pin "1") (pinfunction "1_1") (pintype "passive"))
      (node (ref "U2") (pin "2") (pinfunction "V+_2") (pintype "power_in"))
    )
    (net (code "49") (name "Net-(U2-V-)") (class "Default")
      (node (ref "C3") (pin "2") (pinfunction "2_2") (pintype "passive"))
      (node (ref "U2") (pin "6") (pinfunction "V-_6") (pintype "power_in"))
    )
    (net (code "50") (name "Net-(U3-OUTPUT)") (class "Default")
      (node (ref "D5") (pin "2") (pinfunction "2_2") (pintype "passive"))
      (node (ref "L1") (pin "2") (pinfunction "2_2") (pintype "passive"))
      (node (ref "U3") (pin "2") (pinfunction "OUTPUT_2") (pintype "passive"))
    )
    (net (code "51") (name "Net-(U4-1A)") (class "Default")
      (node (ref "C11") (pin "2") (pinfunction "2_2") (pintype "passive"))
      (node (ref "R8") (pin "1") (pinfunction "1_1") (pintype "passive"))
      (node (ref "U4") (pin "1") (pinfunction "1A_1") (pintype "passive"))
    )
    (net (code "52") (name "Net-(U4-2A)") (class "Default")
      (node (ref "C12") (pin "2") (pinfunction "2_2") (pintype "passive"))
      (node (ref "R9") (pin "1") (pinfunction "1_1") (pintype "passive"))
      (node (ref "U4") (pin "3") (pinfunction "2A_3") (pintype "passive"))
    )
    (net (code "53") (name "Net-(U4-3A)") (class "Default")
      (node (ref "C13") (pin "2") (pinfunction "2_2") (pintype "passive"))
      (node (ref "R10") (pin "1") (pinfunction "1_1") (pintype "passive"))
      (node (ref "U4") (pin "5") (pinfunction "3A_5") (pintype "passive"))
    )
    (net (code "54") (name "Net-(U4-4A)") (class "Default")
      (node (ref "C16") (pin "2") (pinfunction "2_2") (pintype "passive"))
      (node (ref "R18") (pin "1") (pinfunction "1_1") (pintype "passive"))
      (node (ref "U4") (pin "9") (pinfunction "4A_9") (pintype "passive"))
    )
    (net (code "55") (name "Net-(U4-5A)") (class "Default")
      (node (ref "C17") (pin "2") (pinfunction "2_2") (pintype "passive"))
      (node (ref "R19") (pin "1") (pinfunction "1_1") (pintype "passive"))
      (node (ref "U4") (pin "11") (pinfunction "5A_11") (pintype "passive"))
    )
    (net (code "56") (name "Net-(U4-6A)") (class "Default")
      (node (ref "C18") (pin "2") (pinfunction "2_2") (pintype "passive"))
      (node (ref "R20") (pin "1") (pinfunction "1_1") (pintype "passive"))
      (node (ref "U4") (pin "13") (pinfunction "6A_13") (pintype "passive"))
    )
    (net (code "57") (name "Net-(X2-PB0)") (class "Default")
      (node (ref "R23") (pin "2") (pinfunction "2_2") (pintype "passive"))
      (node (ref "X2") (pin "34") (pinfunction "PB0_34") (pintype "passive"))
    )
    (net (code "58") (name "Net-(X2-PB1)") (class "Default")
      (node (ref "R22") (pin "2") (pinfunction "2_2") (pintype "passive"))
      (node (ref "X2") (pin "35") (pinfunction "PB1_35") (pintype "passive"))
    )
    (net (code "59") (name "Net-(X2-PB3)") (class "Default")
      (node (ref "R14") (pin "1") (pinfunction "1_1") (pintype "passive"))
      (node (ref "X2") (pin "11") (pinfunction "PB3_11") (pintype "passive"))
    )
    (net (code "60") (name "Net-(X2-PB4)") (class "Default")
      (node (ref "R15") (pin "1") (pinfunction "1_1") (pintype "passive"))
      (node (ref "X2") (pin "12") (pinfunction "PB4_12") (pintype "passive"))
    )
    (net (code "61") (name "Net-(X2-PB5)") (class "Default")
      (node (ref "R16") (pin "1") (pinfunction "1_1") (pintype "passive"))
      (node (ref "X2") (pin "13") (pinfunction "PB5_13") (pintype "passive"))
    )
    (net (code "62") (name "Net-(X2-PB8)") (class "Default")
      (node (ref "R17") (pin "1") (pinfunction "1_1") (pintype "passive"))
      (node (ref "X2") (pin "16") (pinfunction "PB8_16") (pintype "passive"))
    )
    (net (code "63") (name "unconnected-(U2-DIN2-Pad10)") (class "Default")
      (node (ref "U2") (pin "10") (pinfunction "DIN2_10") (pintype "passive"))
    )
    (net (code "64") (name "unconnected-(U2-DOUT2-Pad7)") (class "Default")
      (node (ref "U2") (pin "7") (pinfunction "DOUT2_7") (pintype "passive"))
    )
    (net (code "65") (name "unconnected-(U2-RIN2-Pad8)") (class "Default")
      (node (ref "U2") (pin "8") (pinfunction "RIN2_8") (pintype "passive"))
    )
    (net (code "66") (name "unconnected-(U2-ROUT2-Pad9)") (class "Default")
      (node (ref "U2") (pin "9") (pinfunction "ROUT2_9") (pintype "passive"))
    )
    (net (code "67") (name "unconnected-(X1-Pad3)") (class "Default")
      (node (ref "X1") (pin "3") (pinfunction "3_3") (pintype "passive"))
    )
    (net (code "68") (name "unconnected-(X1-Pad6)") (class "Default")
      (node (ref "X1") (pin "6") (pinfunction "6_6") (pintype "passive"))
    )
    (net (code "69") (name "unconnected-(X2-3V3-Pad20)") (class "Default")
      (node (ref "X2") (pin "20") (pinfunction "3V3_20") (pintype "passive"))
    )
    (net (code "70") (name "unconnected-(X2-3V3-Pad38)") (class "Default")
      (node (ref "X2") (pin "38") (pinfunction "3V3_38") (pintype "passive"))
    )
    (net (code "71") (name "unconnected-(X2-PB2-Pad36)") (class "Default")
      (node (ref "X2") (pin "36") (pinfunction "PB2_36") (pintype "passive"))
    )
    (net (code "72") (name "unconnected-(X2-PB9-Pad17)") (class "Default")
      (node (ref "X2") (pin "17") (pinfunction "PB9_17") (pintype "passive"))
    )
    (net (code "73") (name "unconnected-(X2-PB10-Pad37)") (class "Default")
      (node (ref "X2") (pin "37") (pinfunction "PB10_37") (pintype "passive"))
    )
    (net (code "74") (name "unconnected-(X2-PC13-Pad22)") (class "Default")
      (node (ref "X2") (pin "22") (pinfunction "PC13_22") (pintype "passive"))
    )
    (net (code "75") (name "unconnected-(X2-PC14-Pad23)") (class "Default")
      (node (ref "X2") (pin "23") (pinfunction "PC14_23") (pintype "passive"))
    )
    (net (code "76") (name "unconnected-(X2-PC15-Pad24)") (class "Default")
      (node (ref "X2") (pin "24") (pinfunction "PC15_24") (pintype "passive"))
    )
    (net (code "77") (name "unconnected-(X2-RST-Pad25)") (class "Default")
      (node (ref "X2") (pin "25") (pinfunction "RST_25") (pintype "passive"))
    )
  )
)
